# CTRL.net
KiCad netlist of a schematic drawn in EAGLE
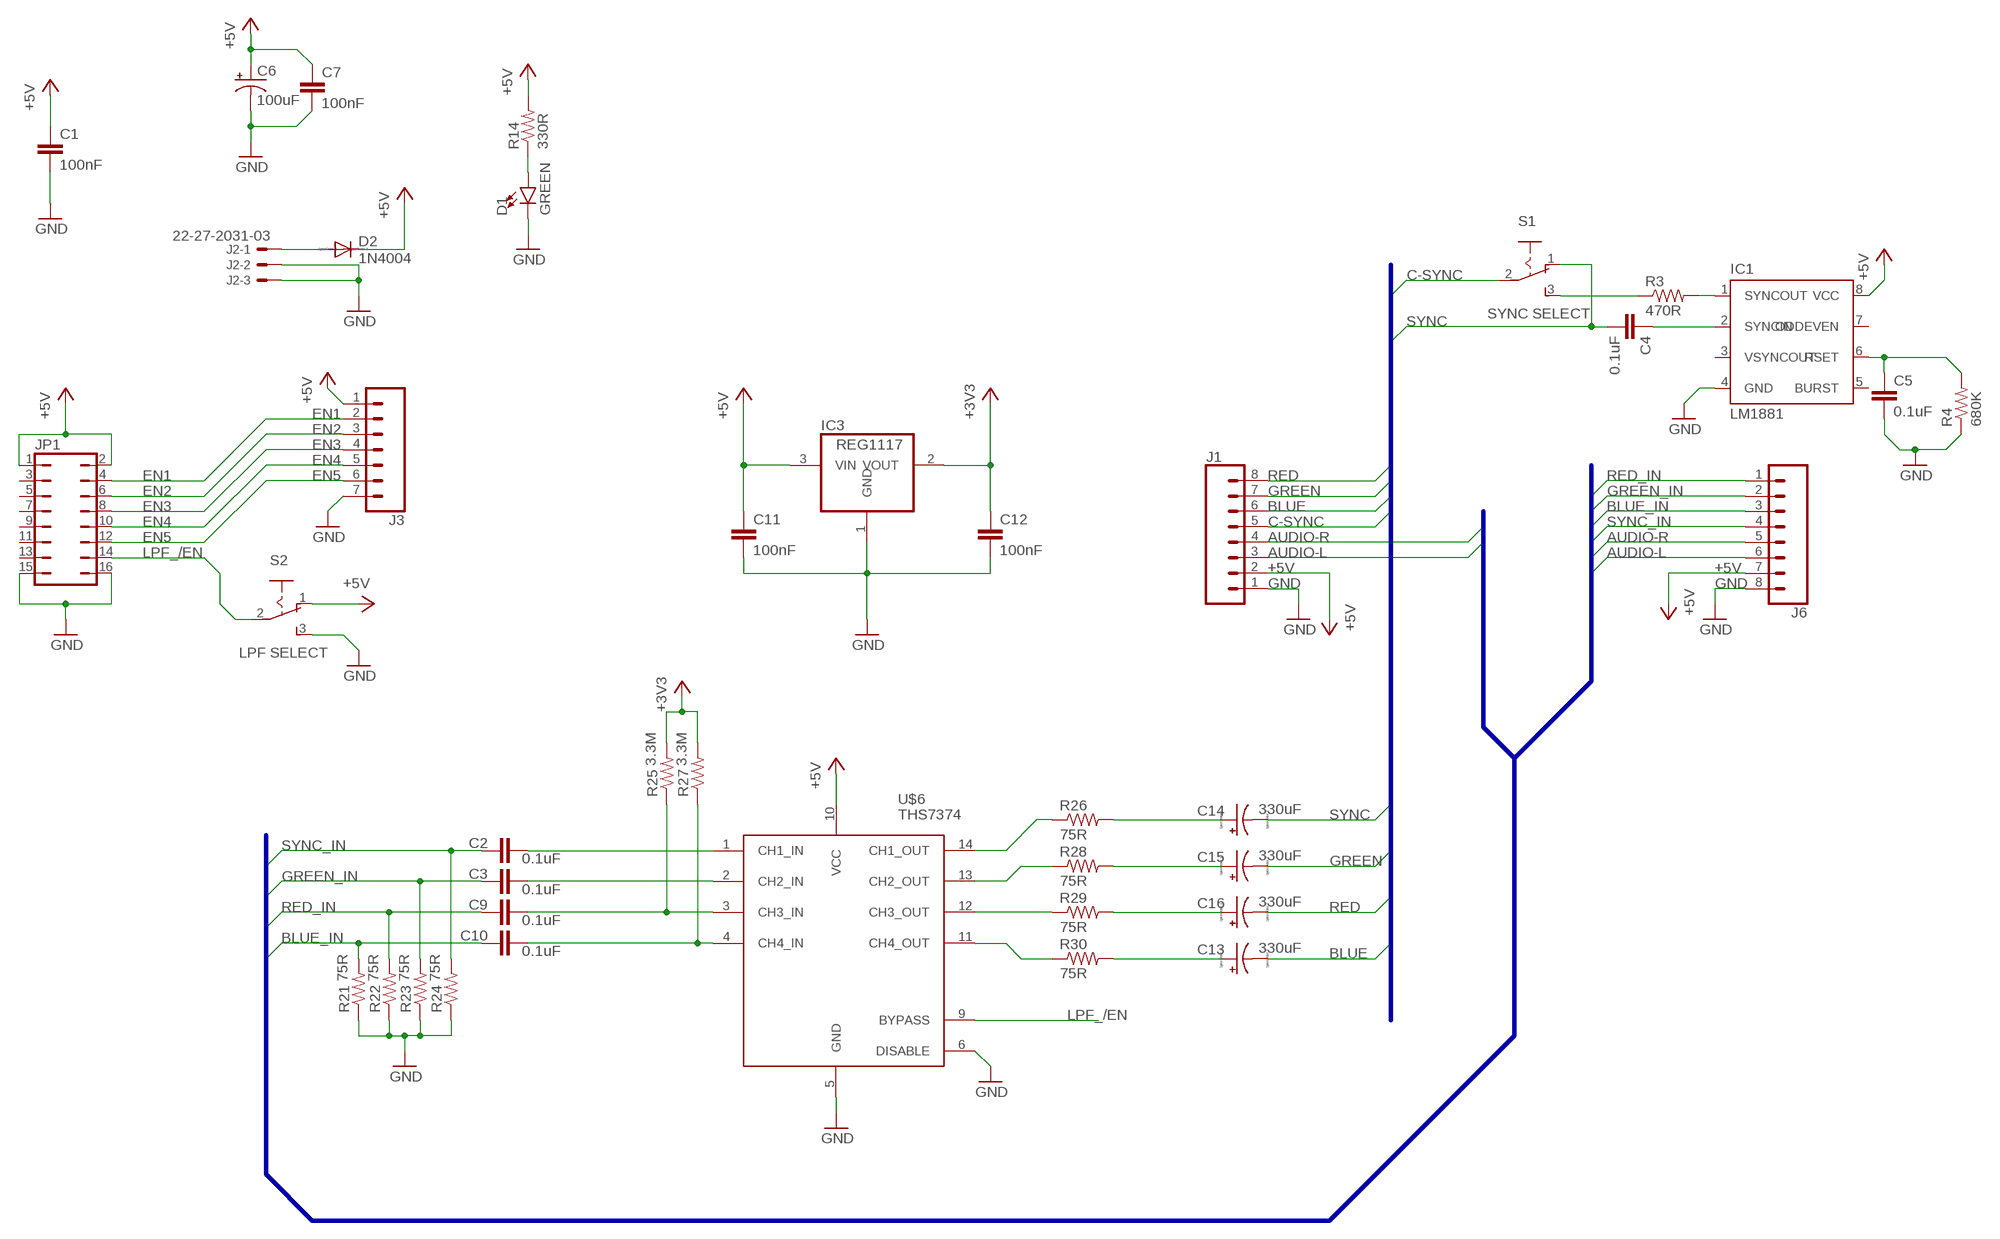
[diagram p0: schematic, sheet 1]

(export (version "E")
  (design (tool "Eeschema 10.0.6"))
  (components
    (comp (ref "C1")
      (value "100nF")
      (footprint "eagle-import:C075-032X103")
      (libsource (lib "eagle-import") (part "C-EU075-032X103"))
    )
    (comp (ref "C2")
      (value "0.1uF")
      (footprint "eagle-import:C050-025X075")
      (libsource (lib "eagle-import") (part "C-EU050-025X075"))
    )
    (comp (ref "C3")
      (value "0.1uF")
      (footprint "eagle-import:C050-025X075")
      (libsource (lib "eagle-import") (part "C-EU050-025X075"))
    )
    (comp (ref "C4")
      (value "0.1uF")
      (footprint "eagle-import:C7.5B3")
      (libsource (lib "eagle-import") (part "C7.5/3"))
    )
    (comp (ref "C5")
      (value "0.1uF")
      (footprint "eagle-import:C7.5B3")
      (libsource (lib "eagle-import") (part "C7.5/3"))
    )
    (comp (ref "C6")
      (value "100uF")
      (footprint "eagle-import:E2,5-7")
      (libsource (lib "eagle-import") (part "CPOL-USE2.5-7"))
    )
    (comp (ref "C7")
      (value "100nF")
      (footprint "eagle-import:C075-032X103")
      (libsource (lib "eagle-import") (part "C-EU075-032X103"))
    )
    (comp (ref "C9")
      (value "0.1uF")
      (footprint "eagle-import:C050-025X075")
      (libsource (lib "eagle-import") (part "C-EU050-025X075"))
    )
    (comp (ref "C10")
      (value "0.1uF")
      (footprint "eagle-import:C050-025X075")
      (libsource (lib "eagle-import") (part "C-EU050-025X075"))
    )
    (comp (ref "C11")
      (value "100nF")
      (footprint "eagle-import:C075-032X103")
      (libsource (lib "eagle-import") (part "C-EU075-032X103"))
    )
    (comp (ref "C12")
      (value "100nF")
      (footprint "eagle-import:C075-032X103")
      (libsource (lib "eagle-import") (part "C-EU075-032X103"))
    )
    (comp (ref "C13")
      (value "330uF")
      (footprint "eagle-import:D_7343-31W")
      (libsource (lib "eagle-import") (part "resistor_CPOL-USD/7343-31W"))
    )
    (comp (ref "C14")
      (value "330uF")
      (footprint "eagle-import:D_7343-31W")
      (libsource (lib "eagle-import") (part "resistor_CPOL-USD/7343-31W"))
    )
    (comp (ref "C15")
      (value "330uF")
      (footprint "eagle-import:D_7343-31W")
      (libsource (lib "eagle-import") (part "resistor_CPOL-USD/7343-31W"))
    )
    (comp (ref "C16")
      (value "330uF")
      (footprint "eagle-import:D_7343-31W")
      (libsource (lib "eagle-import") (part "resistor_CPOL-USD/7343-31W"))
    )
    (comp (ref "D1")
      (value "GREEN")
      (footprint "eagle-import:LED_5MM")
      (libsource (lib "eagle-import") (part "LED5MM"))
    )
    (comp (ref "D2")
      (value "1N4004")
      (footprint "eagle-import:DO41-10")
      (libsource (lib "eagle-import") (part "1N4004"))
    )
    (comp (ref "IC1")
      (value "LM1881")
      (footprint "eagle-import:DIL08")
      (libsource (lib "eagle-import") (part "LM1881"))
    )
    (comp (ref "IC3")
      (value "REG1117")
      (footprint "eagle-import:SOT223")
      (libsource (lib "eagle-import") (part "REG1117"))
    )
    (comp (ref "J1")
      (value "CONN_08LONGPADS")
      (footprint "eagle-import:1X08_LONGPADS")
      (libsource (lib "eagle-import") (part "CONN_08LONGPADS"))
    )
    (comp (ref "J2")
      (value "22-27-2031-03")
      (footprint "eagle-import:6410-03")
      (libsource (lib "eagle-import") (part "22-?-0327-2031"))
    )
    (comp (ref "J3")
      (value "CONN_07LONGPADS")
      (footprint "eagle-import:1X07_LONGPADS")
      (libsource (lib "eagle-import") (part "CONN_07LONGPADS"))
    )
    (comp (ref "J6")
      (value "CONN_08LONGPADS")
      (footprint "eagle-import:1X08_LONGPADS")
      (libsource (lib "eagle-import") (part "CONN_08LONGPADS"))
    )
    (comp (ref "JP1")
      (value "JP8Q")
      (footprint "eagle-import:JP8Q")
      (libsource (lib "eagle-import") (part "JP8Q"))
    )
    (comp (ref "R3")
      (value "470R")
      (footprint "eagle-import:0204_7")
      (libsource (lib "eagle-import") (part "R-US_0204/7"))
    )
    (comp (ref "R4")
      (value "680K")
      (footprint "eagle-import:0204_7")
      (libsource (lib "eagle-import") (part "R-US_0204/7"))
    )
    (comp (ref "R14")
      (value "330R")
      (footprint "eagle-import:0204_7")
      (libsource (lib "eagle-import") (part "resistor_R-US_0204/7"))
    )
    (comp (ref "R21")
      (value "75R")
      (footprint "eagle-import:0204V")
      (libsource (lib "eagle-import") (part "R-US_0204/2V"))
    )
    (comp (ref "R22")
      (value "75R")
      (footprint "eagle-import:0204V")
      (libsource (lib "eagle-import") (part "R-US_0204/2V"))
    )
    (comp (ref "R23")
      (value "75R")
      (footprint "eagle-import:0204V")
      (libsource (lib "eagle-import") (part "R-US_0204/2V"))
    )
    (comp (ref "R24")
      (value "75R")
      (footprint "eagle-import:0204V")
      (libsource (lib "eagle-import") (part "R-US_0204/2V"))
    )
    (comp (ref "R25")
      (value "3.3M")
      (footprint "eagle-import:0204_7")
      (libsource (lib "eagle-import") (part "R-US_0204/7"))
    )
    (comp (ref "R26")
      (value "75R")
      (footprint "eagle-import:0204_7")
      (libsource (lib "eagle-import") (part "R-US_0204/7"))
    )
    (comp (ref "R27")
      (value "3.3M")
      (footprint "eagle-import:0204_7")
      (libsource (lib "eagle-import") (part "R-US_0204/7"))
    )
    (comp (ref "R28")
      (value "75R")
      (footprint "eagle-import:0204_7")
      (libsource (lib "eagle-import") (part "R-US_0204/7"))
    )
    (comp (ref "R29")
      (value "75R")
      (footprint "eagle-import:0204_7")
      (libsource (lib "eagle-import") (part "R-US_0204/7"))
    )
    (comp (ref "R30")
      (value "75R")
      (footprint "eagle-import:0204_7")
      (libsource (lib "eagle-import") (part "R-US_0204/7"))
    )
    (comp (ref "S1")
      (value "SYNC SELECT")
      (footprint "eagle-import:255SB")
      (libsource (lib "eagle-import") (part "255SB"))
    )
    (comp (ref "S2")
      (value "LPF SELECT")
      (footprint "eagle-import:255SB")
      (libsource (lib "eagle-import") (part "255SB"))
    )
    (comp (ref "U$6")
      (value "THS7374")
      (footprint "eagle-import:TSSOP-14")
      (libsource (lib "eagle-import") (part "THS7374"))
    )
  )
  (nets
    (net (code "1") (name "+3V3") (class "Default")
      (node (ref "C12") (pin "1") (pinfunction "1_1") (pintype "passive"))
      (node (ref "IC3") (pin "2") (pinfunction "VOUT_2") (pintype "output"))
      (node (ref "R25") (pin "2") (pinfunction "2_2") (pintype "passive"))
      (node (ref "R27") (pin "2") (pinfunction "2_2") (pintype "passive"))
    )
    (net (code "2") (name "+5V") (class "Default")
      (node (ref "C1") (pin "1") (pinfunction "1_1") (pintype "passive"))
      (node (ref "C11") (pin "1") (pinfunction "1_1") (pintype "passive"))
      (node (ref "C6") (pin "+") (pinfunction "+_+") (pintype "passive"))
      (node (ref "C7") (pin "1") (pinfunction "1_1") (pintype "passive"))
      (node (ref "D2") (pin "C") (pinfunction "C_C") (pintype "passive"))
      (node (ref "IC1") (pin "8") (pinfunction "VCC_8") (pintype "power_in"))
      (node (ref "IC3") (pin "3") (pinfunction "VIN_3") (pintype "input"))
      (node (ref "J1") (pin "2") (pinfunction "2_2") (pintype "passive"))
      (node (ref "J3") (pin "1") (pinfunction "1_1") (pintype "passive"))
      (node (ref "J6") (pin "7") (pinfunction "7_7") (pintype "passive"))
      (node (ref "JP1") (pin "1") (pinfunction "1_1") (pintype "passive"))
      (node (ref "JP1") (pin "2") (pinfunction "2_2") (pintype "passive"))
      (node (ref "R14") (pin "2") (pinfunction "2_2") (pintype "passive"))
      (node (ref "S2") (pin "1") (pinfunction "O_1") (pintype "passive"))
      (node (ref "U$6") (pin "10") (pinfunction "VCC_10") (pintype "power_in"))
    )
    (net (code "3") (name "/AUDIO-L") (class "Default")
      (node (ref "J1") (pin "3") (pinfunction "3_3") (pintype "passive"))
      (node (ref "J6") (pin "6") (pinfunction "6_6") (pintype "passive"))
    )
    (net (code "4") (name "/AUDIO-R") (class "Default")
      (node (ref "J1") (pin "4") (pinfunction "4_4") (pintype "passive"))
      (node (ref "J6") (pin "5") (pinfunction "5_5") (pintype "passive"))
    )
    (net (code "5") (name "/BLUE") (class "Default")
      (node (ref "C13") (pin "-") (pinfunction "-_-") (pintype "passive"))
      (node (ref "J1") (pin "6") (pinfunction "6_6") (pintype "passive"))
    )
    (net (code "6") (name "/BLUE_IN") (class "Default")
      (node (ref "C10") (pin "1") (pinfunction "1_1") (pintype "passive"))
      (node (ref "J6") (pin "3") (pinfunction "3_3") (pintype "passive"))
      (node (ref "R21") (pin "2") (pinfunction "2_2") (pintype "passive"))
    )
    (net (code "7") (name "/C-SYNC") (class "Default")
      (node (ref "J1") (pin "5") (pinfunction "5_5") (pintype "passive"))
      (node (ref "S1") (pin "2") (pinfunction "P_2") (pintype "passive"))
    )
    (net (code "8") (name "/EN1") (class "Default")
      (node (ref "J3") (pin "2") (pinfunction "2_2") (pintype "passive"))
      (node (ref "JP1") (pin "4") (pinfunction "4_4") (pintype "passive"))
    )
    (net (code "9") (name "/EN2") (class "Default")
      (node (ref "J3") (pin "3") (pinfunction "3_3") (pintype "passive"))
      (node (ref "JP1") (pin "6") (pinfunction "6_6") (pintype "passive"))
    )
    (net (code "10") (name "/EN3") (class "Default")
      (node (ref "J3") (pin "4") (pinfunction "4_4") (pintype "passive"))
      (node (ref "JP1") (pin "8") (pinfunction "8_8") (pintype "passive"))
    )
    (net (code "11") (name "/EN4") (class "Default")
      (node (ref "J3") (pin "5") (pinfunction "5_5") (pintype "passive"))
      (node (ref "JP1") (pin "10") (pinfunction "10_10") (pintype "passive"))
    )
    (net (code "12") (name "/EN5") (class "Default")
      (node (ref "J3") (pin "6") (pinfunction "6_6") (pintype "passive"))
      (node (ref "JP1") (pin "12") (pinfunction "12_12") (pintype "passive"))
    )
    (net (code "13") (name "/GREEN") (class "Default")
      (node (ref "C15") (pin "-") (pinfunction "-_-") (pintype "passive"))
      (node (ref "J1") (pin "7") (pinfunction "7_7") (pintype "passive"))
    )
    (net (code "14") (name "/GREEN_IN") (class "Default")
      (node (ref "C3") (pin "1") (pinfunction "1_1") (pintype "passive"))
      (node (ref "J6") (pin "2") (pinfunction "2_2") (pintype "passive"))
      (node (ref "R23") (pin "2") (pinfunction "2_2") (pintype "passive"))
    )
    (net (code "15") (name "/LPF_{slash}EN") (class "Default")
      (node (ref "JP1") (pin "14") (pinfunction "14_14") (pintype "passive"))
      (node (ref "S2") (pin "2") (pinfunction "P_2") (pintype "passive"))
      (node (ref "U$6") (pin "9") (pinfunction "BYPASS_9") (pintype "input"))
    )
    (net (code "16") (name "/RED") (class "Default")
      (node (ref "C16") (pin "-") (pinfunction "-_-") (pintype "passive"))
      (node (ref "J1") (pin "8") (pinfunction "8_8") (pintype "passive"))
    )
    (net (code "17") (name "/RED_IN") (class "Default")
      (node (ref "C9") (pin "1") (pinfunction "1_1") (pintype "passive"))
      (node (ref "J6") (pin "1") (pinfunction "1_1") (pintype "passive"))
      (node (ref "R22") (pin "2") (pinfunction "2_2") (pintype "passive"))
    )
    (net (code "18") (name "/SYNC") (class "Default")
      (node (ref "C14") (pin "-") (pinfunction "-_-") (pintype "passive"))
      (node (ref "C4") (pin "2") (pinfunction "2_2") (pintype "passive"))
      (node (ref "S1") (pin "1") (pinfunction "O_1") (pintype "passive"))
    )
    (net (code "19") (name "/SYNC_IN") (class "Default")
      (node (ref "C2") (pin "1") (pinfunction "1_1") (pintype "passive"))
      (node (ref "J6") (pin "4") (pinfunction "4_4") (pintype "passive"))
      (node (ref "R24") (pin "2") (pinfunction "2_2") (pintype "passive"))
    )
    (net (code "20") (name "GND") (class "Default")
      (node (ref "C1") (pin "2") (pinfunction "2_2") (pintype "passive"))
      (node (ref "C11") (pin "2") (pinfunction "2_2") (pintype "passive"))
      (node (ref "C12") (pin "2") (pinfunction "2_2") (pintype "passive"))
      (node (ref "C5") (pin "2") (pinfunction "2_2") (pintype "passive"))
      (node (ref "C6") (pin "-") (pinfunction "-_-") (pintype "passive"))
      (node (ref "C7") (pin "2") (pinfunction "2_2") (pintype "passive"))
      (node (ref "D1") (pin "K") (pinfunction "C_K") (pintype "passive"))
      (node (ref "IC1") (pin "4") (pinfunction "GND_4") (pintype "power_in"))
      (node (ref "IC3") (pin "1") (pinfunction "GND_1") (pintype "power_in"))
      (node (ref "J1") (pin "1") (pinfunction "1_1") (pintype "passive"))
      (node (ref "J2") (pin "2") (pinfunction "S_2") (pintype "passive"))
      (node (ref "J2") (pin "3") (pinfunction "S_3") (pintype "passive"))
      (node (ref "J3") (pin "7") (pinfunction "7_7") (pintype "passive"))
      (node (ref "J6") (pin "8") (pinfunction "8_8") (pintype "passive"))
      (node (ref "JP1") (pin "15") (pinfunction "15_15") (pintype "passive"))
      (node (ref "JP1") (pin "16") (pinfunction "16_16") (pintype "passive"))
      (node (ref "R21") (pin "1") (pinfunction "1_1") (pintype "passive"))
      (node (ref "R22") (pin "1") (pinfunction "1_1") (pintype "passive"))
      (node (ref "R23") (pin "1") (pinfunction "1_1") (pintype "passive"))
      (node (ref "R24") (pin "1") (pinfunction "1_1") (pintype "passive"))
      (node (ref "R4") (pin "1") (pinfunction "1_1") (pintype "passive"))
      (node (ref "S2") (pin "3") (pinfunction "S_3") (pintype "passive"))
      (node (ref "U$6") (pin "5") (pinfunction "GND_5") (pintype "power_in"))
      (node (ref "U$6") (pin "6") (pinfunction "DISABLE_6") (pintype "input"))
    )
    (net (code "21") (name "Net-(C13-Pad+)") (class "Default")
      (node (ref "C13") (pin "+") (pinfunction "+_+") (pintype "passive"))
      (node (ref "R30") (pin "2") (pinfunction "2_2") (pintype "passive"))
    )
    (net (code "22") (name "Net-(C14-Pad+)") (class "Default")
      (node (ref "C14") (pin "+") (pinfunction "+_+") (pintype "passive"))
      (node (ref "R26") (pin "2") (pinfunction "2_2") (pintype "passive"))
    )
    (net (code "23") (name "Net-(C15-Pad+)") (class "Default")
      (node (ref "C15") (pin "+") (pinfunction "+_+") (pintype "passive"))
      (node (ref "R28") (pin "2") (pinfunction "2_2") (pintype "passive"))
    )
    (net (code "24") (name "Net-(C16-Pad+)") (class "Default")
      (node (ref "C16") (pin "+") (pinfunction "+_+") (pintype "passive"))
      (node (ref "R29") (pin "2") (pinfunction "2_2") (pintype "passive"))
    )
    (net (code "25") (name "Net-(D1-PadA)") (class "Default")
      (node (ref "D1") (pin "A") (pinfunction "A_A") (pintype "passive"))
      (node (ref "R14") (pin "1") (pinfunction "1_1") (pintype "passive"))
    )
    (net (code "26") (name "Net-(IC1-RSET)") (class "Default")
      (node (ref "C5") (pin "1") (pinfunction "1_1") (pintype "passive"))
      (node (ref "IC1") (pin "6") (pinfunction "RSET_6") (pintype "output"))
      (node (ref "R4") (pin "2") (pinfunction "2_2") (pintype "passive"))
    )
    (net (code "27") (name "Net-(IC1-SYNCIN)") (class "Default")
      (node (ref "C4") (pin "1") (pinfunction "1_1") (pintype "passive"))
      (node (ref "IC1") (pin "2") (pinfunction "SYNCIN_2") (pintype "input"))
    )
    (net (code "28") (name "Net-(IC1-SYNCOUT)") (class "Default")
      (node (ref "IC1") (pin "1") (pinfunction "SYNCOUT_1") (pintype "output"))
      (node (ref "R3") (pin "2") (pinfunction "2_2") (pintype "passive"))
    )
    (net (code "29") (name "Net-(J2A-S)") (class "Default")
      (node (ref "D2") (pin "A") (pinfunction "A_A") (pintype "passive"))
      (node (ref "J2") (pin "1") (pinfunction "S_1") (pintype "passive"))
    )
    (net (code "30") (name "Net-(S1-S)") (class "Default")
      (node (ref "R3") (pin "1") (pinfunction "1_1") (pintype "passive"))
      (node (ref "S1") (pin "3") (pinfunction "S_3") (pintype "passive"))
    )
    (net (code "31") (name "Net-(U$6-CH1_IN)") (class "Default")
      (node (ref "C2") (pin "2") (pinfunction "2_2") (pintype "passive"))
      (node (ref "U$6") (pin "1") (pinfunction "CH1_IN_1") (pintype "input"))
    )
    (net (code "32") (name "Net-(U$6-CH1_OUT)") (class "Default")
      (node (ref "R26") (pin "1") (pinfunction "1_1") (pintype "passive"))
      (node (ref "U$6") (pin "14") (pinfunction "CH1_OUT_14") (pintype "output"))
    )
    (net (code "33") (name "Net-(U$6-CH2_IN)") (class "Default")
      (node (ref "C3") (pin "2") (pinfunction "2_2") (pintype "passive"))
      (node (ref "U$6") (pin "2") (pinfunction "CH2_IN_2") (pintype "input"))
    )
    (net (code "34") (name "Net-(U$6-CH2_OUT)") (class "Default")
      (node (ref "R28") (pin "1") (pinfunction "1_1") (pintype "passive"))
      (node (ref "U$6") (pin "13") (pinfunction "CH2_OUT_13") (pintype "output"))
    )
    (net (code "35") (name "Net-(U$6-CH3_IN)") (class "Default")
      (node (ref "C9") (pin "2") (pinfunction "2_2") (pintype "passive"))
      (node (ref "R25") (pin "1") (pinfunction "1_1") (pintype "passive"))
      (node (ref "U$6") (pin "3") (pinfunction "CH3_IN_3") (pintype "input"))
    )
    (net (code "36") (name "Net-(U$6-CH3_OUT)") (class "Default")
      (node (ref "R29") (pin "1") (pinfunction "1_1") (pintype "passive"))
      (node (ref "U$6") (pin "12") (pinfunction "CH3_OUT_12") (pintype "output"))
    )
    (net (code "37") (name "Net-(U$6-CH4_IN)") (class "Default")
      (node (ref "C10") (pin "2") (pinfunction "2_2") (pintype "passive"))
      (node (ref "R27") (pin "1") (pinfunction "1_1") (pintype "passive"))
      (node (ref "U$6") (pin "4") (pinfunction "CH4_IN_4") (pintype "input"))
    )
    (net (code "38") (name "Net-(U$6-CH4_OUT)") (class "Default")
      (node (ref "R30") (pin "1") (pinfunction "1_1") (pintype "passive"))
      (node (ref "U$6") (pin "11") (pinfunction "CH4_OUT_11") (pintype "output"))
    )
    (net (code "39") (name "unconnected-(IC1-BURST-Pad5)") (class "Default")
      (node (ref "IC1") (pin "5") (pinfunction "BURST_5") (pintype "output"))
    )
    (net (code "40") (name "unconnected-(IC1-ODDEVEN-Pad7)") (class "Default")
      (node (ref "IC1") (pin "7") (pinfunction "ODDEVEN_7") (pintype "output"))
    )
    (net (code "41") (name "unconnected-(IC1-VSYNCOUT-Pad3)") (class "Default")
      (node (ref "IC1") (pin "3") (pinfunction "VSYNCOUT_3") (pintype "output"))
    )
    (net (code "42") (name "unconnected-(JP1-Pad3)") (class "Default")
      (node (ref "JP1") (pin "3") (pinfunction "3_3") (pintype "passive"))
    )
    (net (code "43") (name "unconnected-(JP1-Pad5)") (class "Default")
      (node (ref "JP1") (pin "5") (pinfunction "5_5") (pintype "passive"))
    )
    (net (code "44") (name "unconnected-(JP1-Pad7)") (class "Default")
      (node (ref "JP1") (pin "7") (pinfunction "7_7") (pintype "passive"))
    )
    (net (code "45") (name "unconnected-(JP1-Pad9)") (class "Default")
      (node (ref "JP1") (pin "9") (pinfunction "9_9") (pintype "passive"))
    )
    (net (code "46") (name "unconnected-(JP1-Pad11)") (class "Default")
      (node (ref "JP1") (pin "11") (pinfunction "11_11") (pintype "passive"))
    )
    (net (code "47") (name "unconnected-(JP1-Pad13)") (class "Default")
      (node (ref "JP1") (pin "13") (pinfunction "13_13") (pintype "passive"))
    )
  )
)
